# Schematic_Diagram.net
KiCad netlist of a schematic drawn in EasyEDA
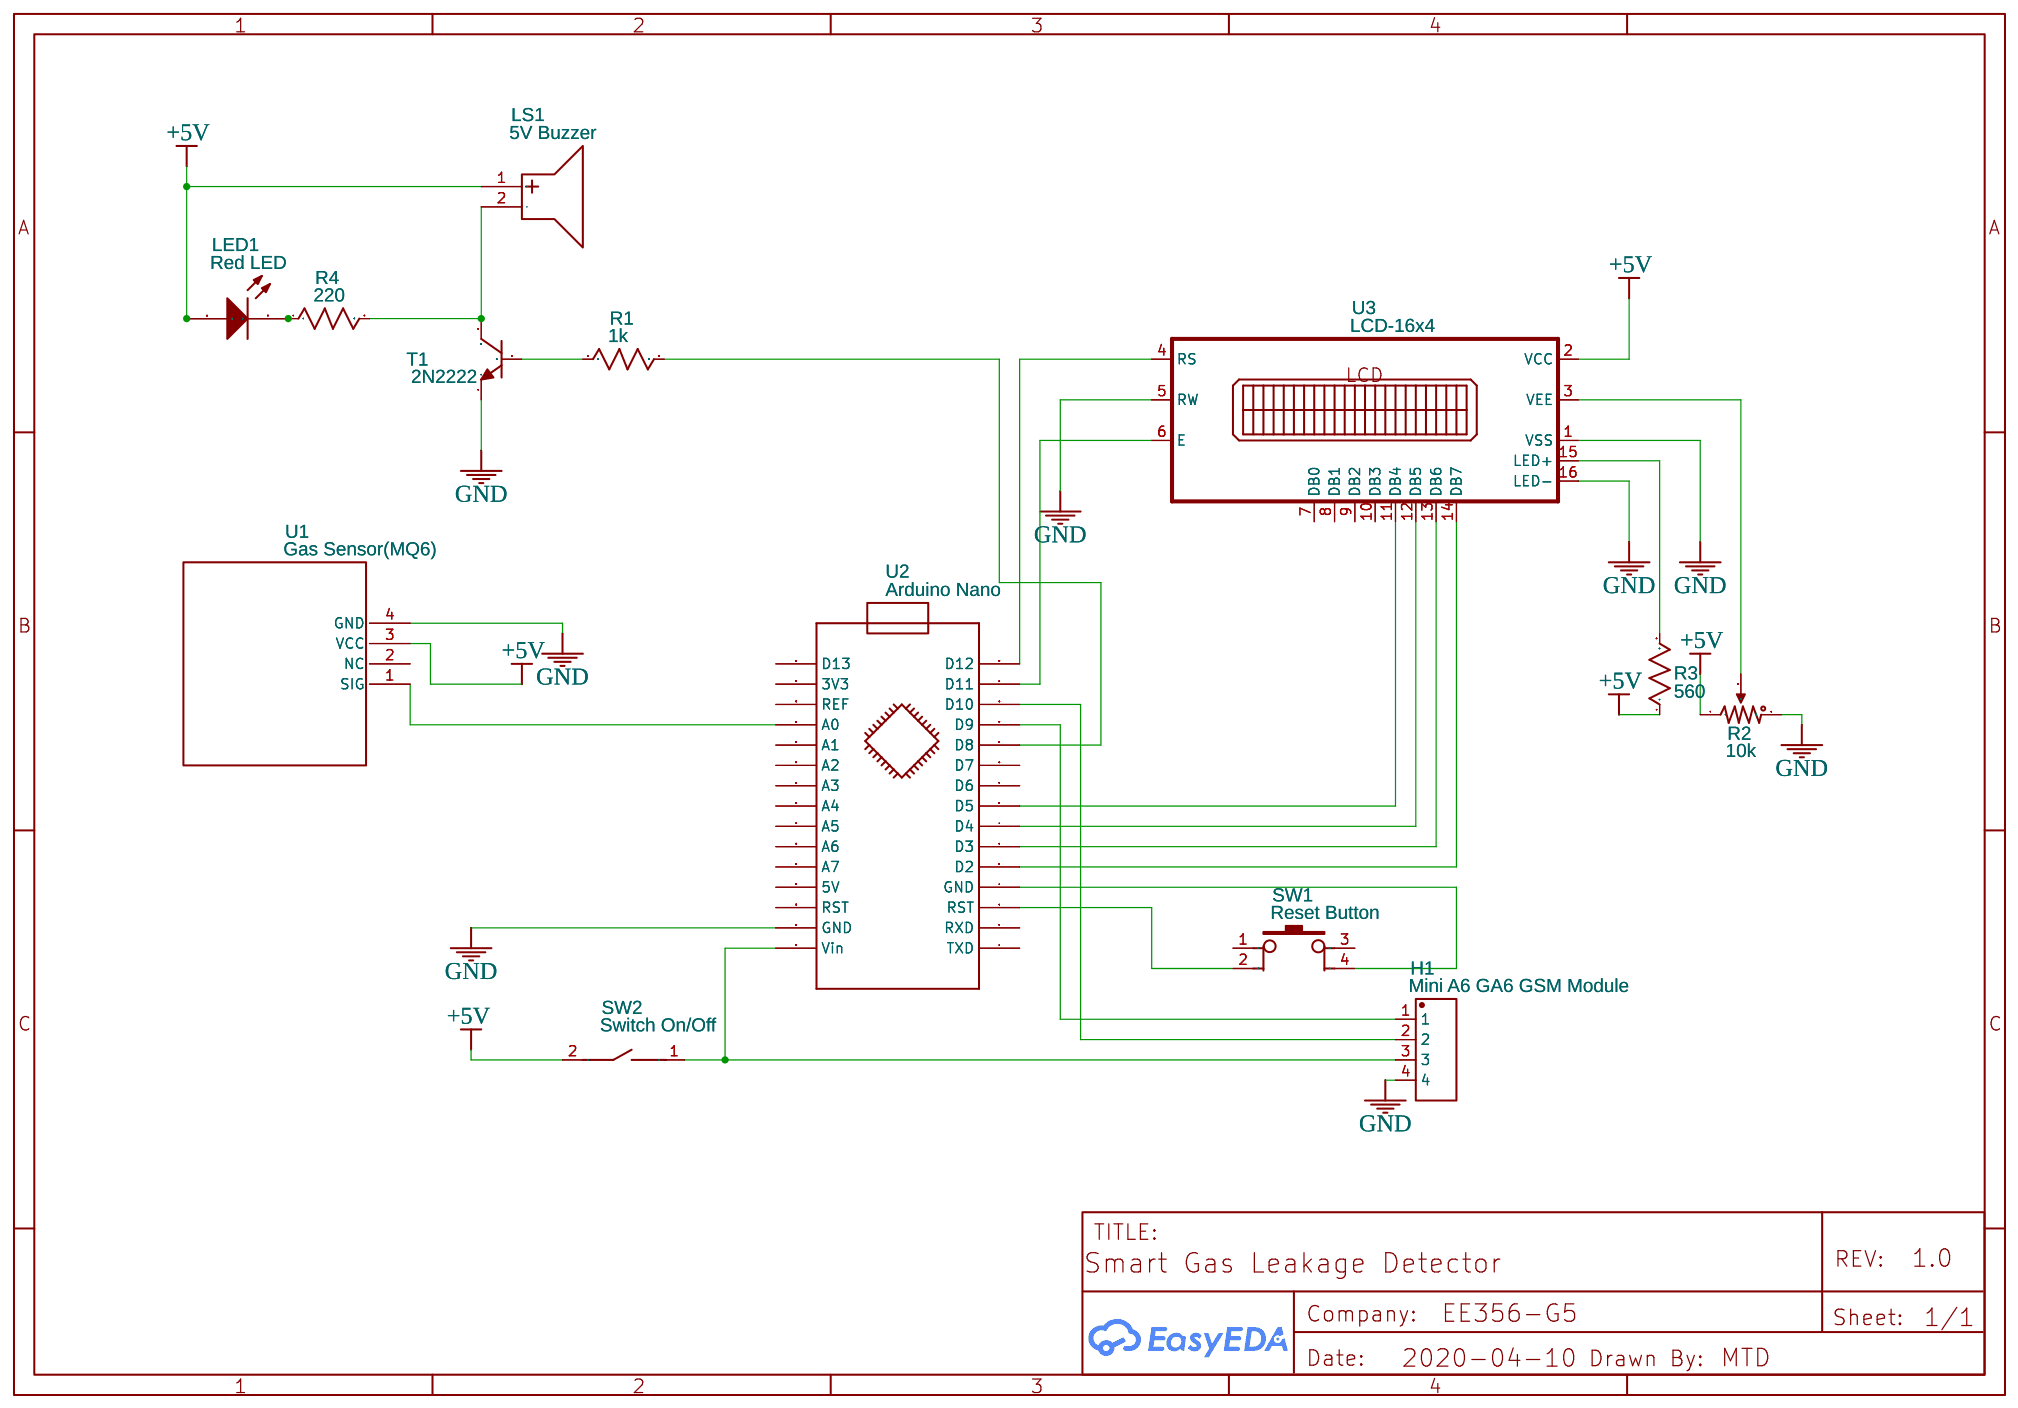
[diagram p0: schematic sheet]

(export (version "E")
  (design (tool "Eeschema 10.0.6"))
  (components
    (comp (ref "H1")
      (value "Mini A6 GA6 GSM Module")
      (fields
        (field (name "BOM_Manufacturer Part") "Headers  Pins 1*4P")
        (field (name "BOM_Supplier Part") "C59481")
      )
      (libsource (lib "") (part "Unknown_890_650"))
    )
    (comp (ref "LED1")
      (value "Red LED")
      (fields (field (name "BOM_Manufacturer Part") "F5Red LED") (field (name "BOM_Supplier Part") "C10500"))
      (libsource (lib "") (part "F5Red LED"))
    )
    (comp (ref "LS1")
      (value "5V Buzzer")
      (fields
        (field (name "BOM_Manufacturer Part") "GMD9505RB-3V2700")
        (field (name "BOM_Supplier Part") "C252935")
      )
      (libsource (lib "") (part "Unknown_445_235"))
    )
    (comp (ref "R1") (value "1k") (libsource (lib "") (part "Res_AXIAL-0.3(1/8W)_US")))
    (comp (ref "R2") (value "10k") (libsource (lib "") (part "Potentiometer")))
    (comp (ref "R3") (value "560") (libsource (lib "") (part "Res_AXIAL-0.3(1/8W)_US_1")))
    (comp (ref "R4") (value "220") (libsource (lib "") (part "Res_AXIAL-0.3(1/8W)_US")))
    (comp (ref "SW1")
      (value "Reset Button")
      (fields
        (field (name "BOM_Manufacturer Part") "6×6×5mm RHOS")
        (field (name "BOM_Supplier Part") "C21456")
      )
      (libsource (lib "") (part "Button-SMD-6×6×5mm"))
    )
    (comp (ref "SW2")
      (value "Switch On/Off")
      (fields
        (field (name "BOM_Manufacturer Part") "Switch,6*6*5Plastic head,260G, 0.25mm,DIP2")
        (field (name "BOM_Supplier Part") "C71845")
      )
      (libsource (lib "") (part "SWITCH,6*6*5PLASTIC HEAD,260G, 0.25MM,DIP2"))
    )
    (comp (ref "T1")
      (value "2N2222")
      (fields (field (name "BOM_Manufacturer Part") "2N3904") (field (name "BOM_Supplier Part") "C118538"))
      (libsource (lib "") (part "Unknown_435_310"))
    )
    (comp (ref "U1")
      (value "Gas Sensor(MQ6)")
      (fields (field (name "BOM_Supplier Part") "undefined"))
      (libsource (lib "") (part "Unknown_335_460"))
    )
    (comp (ref "U2")
      (value "Arduino Nano")
      (fields (field (name "BOM_Manufacturer Part") "?"))
      (libsource (lib "") (part "Unknown_570_440"))
    )
    (comp (ref "U3") (value "LCD-16x4") (libsource (lib "") (part "Unknown_860_350")))
  )
  (nets
    (net (code "1") (name "+5V") (class "Default")
      (node (ref "LED1") (pin "3") (pinfunction "A_3") (pintype "unspecified"))
      (node (ref "LED1") (pin "4") (pinfunction "A_4") (pintype "unspecified"))
      (node (ref "LS1") (pin "1") (pinfunction "+_1") (pintype "unspecified"))
      (node (ref "R2") (pin "1") (pinfunction "1_1") (pintype "unspecified"))
      (node (ref "R3") (pin "1") (pinfunction "1_1") (pintype "unspecified"))
      (node (ref "SW2") (pin "2") (pinfunction "2_2") (pintype "unspecified"))
      (node (ref "U1") (pin "3") (pinfunction "VCC_3") (pintype "unspecified"))
      (node (ref "U3") (pin "2") (pinfunction "VCC_2") (pintype "passive"))
    )
    (net (code "2") (name "GND") (class "Default")
      (node (ref "H1") (pin "4") (pinfunction "4_4") (pintype "unspecified"))
      (node (ref "R2") (pin "3") (pinfunction "2_3") (pintype "unspecified"))
      (node (ref "T1") (pin "1") (pinfunction "E_1") (pintype "unspecified"))
      (node (ref "U1") (pin "4") (pinfunction "GND_4") (pintype "unspecified"))
      (node (ref "U2") (pin "29") (pinfunction "GND_29") (pintype "unspecified"))
      (node (ref "U3") (pin "1") (pinfunction "VSS_1") (pintype "passive"))
      (node (ref "U3") (pin "16") (pinfunction "LED-_16") (pintype "unspecified"))
      (node (ref "U3") (pin "5") (pinfunction "RW_5") (pintype "input"))
    )
    (net (code "3") (name "Net-(LED1-K)") (class "Default")
      (node (ref "LED1") (pin "1") (pinfunction "k_1") (pintype "unspecified"))
      (node (ref "LED1") (pin "2") (pinfunction "K_2") (pintype "unspecified"))
      (node (ref "R4") (pin "1") (pinfunction "1_1") (pintype "unspecified"))
    )
    (net (code "4") (name "Net-(LS1--)") (class "Default")
      (node (ref "LS1") (pin "2") (pinfunction "-_2") (pintype "unspecified"))
      (node (ref "R4") (pin "2") (pinfunction "2_2") (pintype "unspecified"))
      (node (ref "T1") (pin "3") (pinfunction "C_3") (pintype "unspecified"))
    )
    (net (code "5") (name "Net-(R2-3)") (class "Default")
      (node (ref "R2") (pin "2") (pinfunction "3_2") (pintype "unspecified"))
      (node (ref "U3") (pin "3") (pinfunction "VEE_3") (pintype "passive"))
    )
    (net (code "6") (name "Net-(SW1-Pad2)") (class "Default")
      (node (ref "SW1") (pin "2") (pinfunction "2_2") (pintype "input"))
      (node (ref "U2") (pin "3") (pinfunction "RST_3") (pintype "unspecified"))
    )
    (net (code "7") (name "Net-(SW1-Pad4)") (class "Default")
      (node (ref "SW1") (pin "4") (pinfunction "4_4") (pintype "input"))
      (node (ref "U2") (pin "4") (pinfunction "GND_4") (pintype "unspecified"))
    )
    (net (code "8") (name "Net-(T1-B)") (class "Default")
      (node (ref "R1") (pin "1") (pinfunction "1_1") (pintype "unspecified"))
      (node (ref "T1") (pin "2") (pinfunction "B_2") (pintype "unspecified"))
    )
    (net (code "9") (name "Net-(U1-SIG)") (class "Default")
      (node (ref "U1") (pin "1") (pinfunction "SIG_1") (pintype "unspecified"))
      (node (ref "U2") (pin "19") (pinfunction "A0_19") (pintype "unspecified"))
    )
    (net (code "10") (name "Net-(U2-D2)") (class "Default")
      (node (ref "U2") (pin "5") (pinfunction "D2_5") (pintype "unspecified"))
      (node (ref "U3") (pin "14") (pinfunction "DB7_14") (pintype "unspecified"))
    )
    (net (code "11") (name "Net-(U2-D3)") (class "Default")
      (node (ref "U2") (pin "6") (pinfunction "D3_6") (pintype "unspecified"))
      (node (ref "U3") (pin "13") (pinfunction "DB6_13") (pintype "unspecified"))
    )
    (net (code "12") (name "Net-(U2-D4)") (class "Default")
      (node (ref "U2") (pin "7") (pinfunction "D4_7") (pintype "unspecified"))
      (node (ref "U3") (pin "12") (pinfunction "DB5_12") (pintype "unspecified"))
    )
    (net (code "13") (name "Net-(U2-D5)") (class "Default")
      (node (ref "U2") (pin "8") (pinfunction "D5_8") (pintype "unspecified"))
      (node (ref "U3") (pin "11") (pinfunction "DB4_11") (pintype "unspecified"))
    )
    (net (code "14") (name "Net-(U2-D8)") (class "Default")
      (node (ref "R1") (pin "2") (pinfunction "2_2") (pintype "unspecified"))
      (node (ref "U2") (pin "11") (pinfunction "D8_11") (pintype "unspecified"))
    )
    (net (code "15") (name "Net-(U2-D9)") (class "Default")
      (node (ref "H1") (pin "1") (pinfunction "1_1") (pintype "unspecified"))
      (node (ref "U2") (pin "12") (pinfunction "D9_12") (pintype "unspecified"))
    )
    (net (code "16") (name "Net-(U2-D10)") (class "Default")
      (node (ref "H1") (pin "2") (pinfunction "2_2") (pintype "unspecified"))
      (node (ref "U2") (pin "13") (pinfunction "D10_13") (pintype "unspecified"))
    )
    (net (code "17") (name "Net-(U2-D11)") (class "Default")
      (node (ref "U2") (pin "14") (pinfunction "D11_14") (pintype "unspecified"))
      (node (ref "U3") (pin "6") (pinfunction "E_6") (pintype "input"))
    )
    (net (code "18") (name "Net-(U2-D12)") (class "Default")
      (node (ref "U2") (pin "15") (pinfunction "D12_15") (pintype "unspecified"))
      (node (ref "U3") (pin "4") (pinfunction "RS_4") (pintype "input"))
    )
    (net (code "19") (name "Net-(U2-Vin)") (class "Default")
      (node (ref "H1") (pin "3") (pinfunction "3_3") (pintype "unspecified"))
      (node (ref "SW2") (pin "1") (pinfunction "1_1") (pintype "unspecified"))
      (node (ref "U2") (pin "30") (pinfunction "Vin_30") (pintype "unspecified"))
    )
    (net (code "20") (name "Net-(U3-LED+)") (class "Default")
      (node (ref "R3") (pin "2") (pinfunction "2_2") (pintype "unspecified"))
      (node (ref "U3") (pin "15") (pinfunction "LED+_15") (pintype "unspecified"))
    )
    (net (code "21") (name "unconnected-(SW1-Pad1)") (class "Default")
      (node (ref "SW1") (pin "1") (pinfunction "1_1") (pintype "input"))
    )
    (net (code "22") (name "unconnected-(SW1-Pad3)") (class "Default")
      (node (ref "SW1") (pin "3") (pinfunction "3_3") (pintype "input"))
    )
    (net (code "23") (name "unconnected-(U1-NC-Pad2)") (class "Default")
      (node (ref "U1") (pin "2") (pinfunction "NC_2") (pintype "unspecified"))
    )
    (net (code "24") (name "unconnected-(U2-3V3-Pad17)") (class "Default")
      (node (ref "U2") (pin "17") (pinfunction "3V3_17") (pintype "unspecified"))
    )
    (net (code "25") (name "unconnected-(U2-5V-Pad27)") (class "Default")
      (node (ref "U2") (pin "27") (pinfunction "5V_27") (pintype "unspecified"))
    )
    (net (code "26") (name "unconnected-(U2-A1-Pad20)") (class "Default")
      (node (ref "U2") (pin "20") (pinfunction "A1_20") (pintype "unspecified"))
    )
    (net (code "27") (name "unconnected-(U2-A2-Pad21)") (class "Default")
      (node (ref "U2") (pin "21") (pinfunction "A2_21") (pintype "unspecified"))
    )
    (net (code "28") (name "unconnected-(U2-A3-Pad22)") (class "Default")
      (node (ref "U2") (pin "22") (pinfunction "A3_22") (pintype "unspecified"))
    )
    (net (code "29") (name "unconnected-(U2-A4-Pad12)") (class "Default")
      (node (ref "U2") (pin "12") (pinfunction "A4_12") (pintype "unspecified"))
    )
    (net (code "30") (name "unconnected-(U2-A5-Pad14)") (class "Default")
      (node (ref "U2") (pin "14") (pinfunction "A5_14") (pintype "unspecified"))
    )
    (net (code "31") (name "unconnected-(U2-A6-Pad25)") (class "Default")
      (node (ref "U2") (pin "25") (pinfunction "A6_25") (pintype "unspecified"))
    )
    (net (code "32") (name "unconnected-(U2-A7-Pad26)") (class "Default")
      (node (ref "U2") (pin "26") (pinfunction "A7_26") (pintype "unspecified"))
    )
    (net (code "33") (name "unconnected-(U2-D6-Pad9)") (class "Default")
      (node (ref "U2") (pin "9") (pinfunction "D6_9") (pintype "unspecified"))
    )
    (net (code "34") (name "unconnected-(U2-D7-Pad10)") (class "Default")
      (node (ref "U2") (pin "10") (pinfunction "D7_10") (pintype "unspecified"))
    )
    (net (code "35") (name "unconnected-(U2-D13-Pad16)") (class "Default")
      (node (ref "U2") (pin "16") (pinfunction "D13_16") (pintype "unspecified"))
    )
    (net (code "36") (name "unconnected-(U2-REF-Pad18)") (class "Default")
      (node (ref "U2") (pin "18") (pinfunction "REF_18") (pintype "unspecified"))
    )
    (net (code "37") (name "unconnected-(U2-RST-Pad28)") (class "Default")
      (node (ref "U2") (pin "28") (pinfunction "RST_28") (pintype "unspecified"))
    )
    (net (code "38") (name "unconnected-(U2-RXD-Pad2)") (class "Default")
      (node (ref "U2") (pin "2") (pinfunction "RXD_2") (pintype "unspecified"))
    )
    (net (code "39") (name "unconnected-(U2-TXD-Pad1)") (class "Default")
      (node (ref "U2") (pin "1") (pinfunction "TXD_1") (pintype "unspecified"))
    )
    (net (code "40") (name "unconnected-(U3-DB0-Pad7)") (class "Default")
      (node (ref "U3") (pin "7") (pinfunction "DB0_7") (pintype "unspecified"))
    )
    (net (code "41") (name "unconnected-(U3-DB1-Pad8)") (class "Default")
      (node (ref "U3") (pin "8") (pinfunction "DB1_8") (pintype "unspecified"))
    )
    (net (code "42") (name "unconnected-(U3-DB2-Pad9)") (class "Default")
      (node (ref "U3") (pin "9") (pinfunction "DB2_9") (pintype "unspecified"))
    )
    (net (code "43") (name "unconnected-(U3-DB3-Pad10)") (class "Default")
      (node (ref "U3") (pin "10") (pinfunction "DB3_10") (pintype "unspecified"))
    )
  )
)
